# CAN_Transceiver_SN65HVD232D_Angle_Connec.net
KiCad netlist of a schematic drawn in Altium Designer
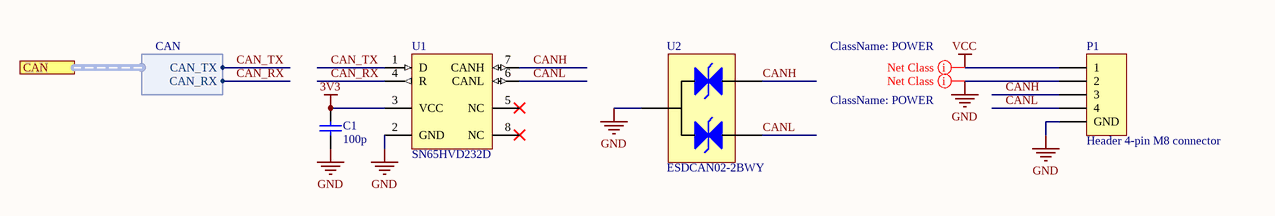
[diagram p0: CAN Transceiver SN65HVD232D Angle Connector.SchDoc]

(export (version "E")
  (design (tool "Eeschema 10.0.6"))
  (components
    (comp (ref "C1")
      (value "100p")
      (footprint "agh_racing_2018:CAP_0603_IPC_MD")
      (description "Capacitor")
      (fields (field (name "Comment") "Cap"))
      (libsource (lib "agh_racing_2018") (part "Cap"))
    )
    (comp (ref "P1")
      (value "Header 4-pin M8 connector")
      (footprint "M8S-04PMMR-SF8001")
      (description "Header, 4-pin M8 connector")
      (libsource (lib "agh_racing_2018") (part "Header 4-pin M8 connector"))
    )
    (comp (ref "U1")
      (value "SN65HVD232D")
      (footprint "agh_racing_2018:SOIC_8_IPC_MD")
      (libsource (lib "agh_racing_2018") (part "SN65HVD232D"))
    )
    (comp (ref "U2")
      (value "ESDCAN02-2BWY")
      (footprint "SOT23_IPC_MD")
      (description "ESD CAN protection (2 transils)")
      (libsource (lib "agh_racing_2018") (part "ESDCAN02-2BWY"))
    )
  )
  (nets
    (net (code "2") (name "/CANH") (class "Default")
      (node (ref "P1") (pin "3") (pinfunction "3_3") (pintype "passive"))
      (node (ref "U1") (pin "7") (pinfunction "CANH_7") (pintype "bidirectional"))
      (node (ref "U2") (pin "1") (pinfunction "IN1_1") (pintype "passive"))
    )
    (net (code "3") (name "/CANL") (class "Default")
      (node (ref "P1") (pin "4") (pinfunction "4_4") (pintype "passive"))
      (node (ref "U1") (pin "6") (pinfunction "CANL_6") (pintype "bidirectional"))
      (node (ref "U2") (pin "2") (pinfunction "IN2_2") (pintype "passive"))
    )
    (net (code "4") (name "/CAN_RX") (class "Default")
      (node (ref "U1") (pin "4") (pinfunction "R_4") (pintype "output"))
    )
    (net (code "5") (name "/CAN_TX") (class "Default")
      (node (ref "U1") (pin "1") (pinfunction "D_1") (pintype "input"))
    )
    (net (code "7") (name "3V3") (class "Default")
      (node (ref "C1") (pin "2") (pinfunction "2_2") (pintype "passive"))
      (node (ref "U1") (pin "3") (pinfunction "VCC_3") (pintype "power_in"))
    )
    (net (code "8") (name "GND") (class "Default")
      (node (ref "C1") (pin "1") (pinfunction "1_1") (pintype "passive"))
      (node (ref "P1") (pin "2") (pinfunction "2_2") (pintype "passive"))
      (node (ref "P1") (pin "GND") (pinfunction "GND_GND") (pintype "passive"))
      (node (ref "U1") (pin "2") (pinfunction "GND_2") (pintype "power_in"))
      (node (ref "U2") (pin "3") (pinfunction "COM_3") (pintype "passive"))
    )
    (net (code "9") (name "VCC") (class "Default")
      (node (ref "P1") (pin "1") (pinfunction "1_1") (pintype "passive"))
    )
    (net (code "10") (name "unconnected-(U1-NC-Pad5)") (class "Default")
      (node (ref "U1") (pin "5") (pinfunction "NC_5") (pintype "passive+no_connect"))
    )
    (net (code "11") (name "unconnected-(U1-NC-Pad8)") (class "Default")
      (node (ref "U1") (pin "8") (pinfunction "NC_8") (pintype "passive+no_connect"))
    )
  )
)
